# MAIN_POWER.net
KiCad netlist of a schematic drawn in Altium Designer
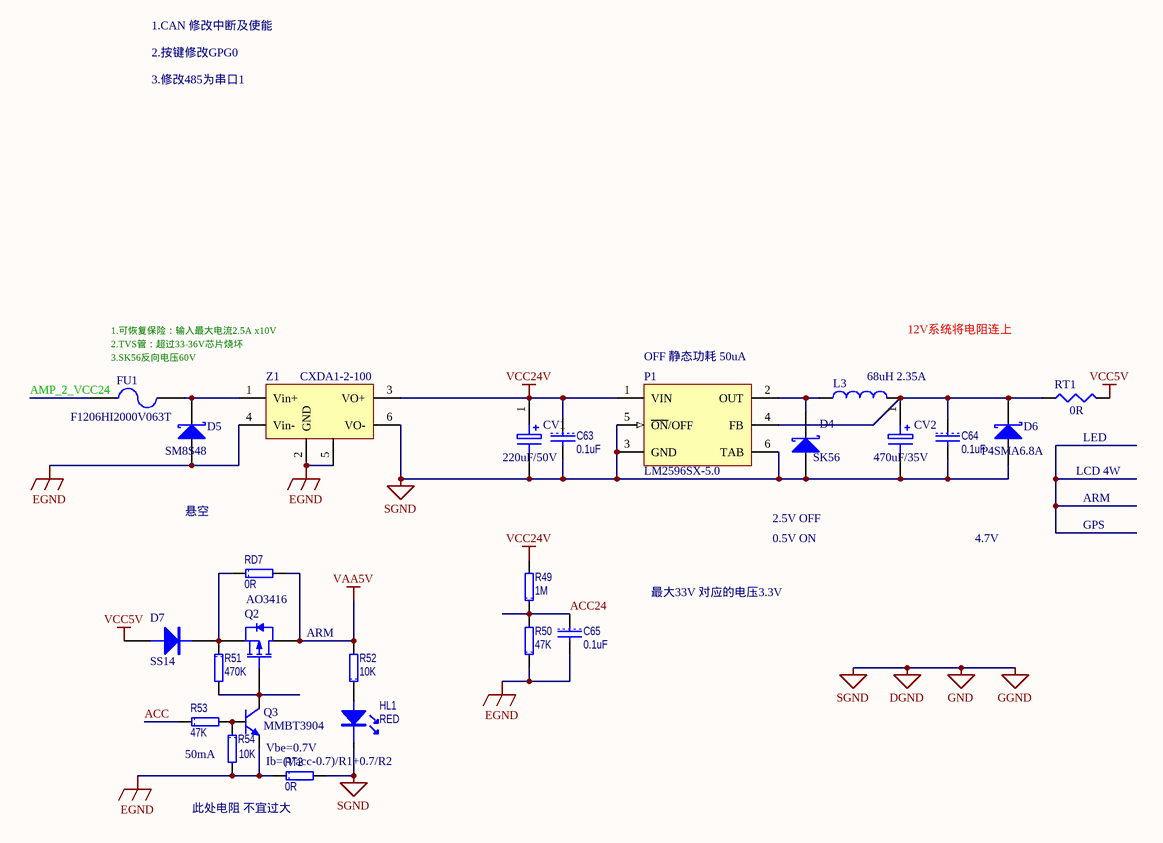
[diagram p0: MAIN POWER.SchDoc]

(export (version "E")
  (design (tool "Eeschema 10.0.6"))
  (components
    (comp (ref "C63")
      (value "0.1uF")
      (footprint "1608[0603]")
      (description "Capacitor")
      (fields (field (name "MANUFACTURER") "TDK"))
      (libsource (lib "*") (part "CAP"))
    )
    (comp (ref "C64")
      (value "0.1uF")
      (footprint "1608[0603]")
      (description "Capacitor")
      (fields (field (name "MANUFACTURER") "TDK"))
      (libsource (lib "*") (part "CAP"))
    )
    (comp (ref "C65")
      (value "0.1uF")
      (footprint "1608[0603]")
      (description "Capacitor")
      (fields (field (name "MANUFACTURER") "TDK"))
      (libsource (lib "*") (part "CAP"))
    )
    (comp (ref "CV1")
      (value "220uF/50V")
      (footprint "CAPPR5-10x20/H1.1")
      (description "aluminum electrolytic capacitor")
      (fields (field (name "MANUFACTURER") "Yageo"))
      (libsource (lib "*") (part "ELECTRO1"))
    )
    (comp (ref "CV2")
      (value "470uF/35V")
      (footprint "CAPPR5-10x20/H1.1")
      (description "aluminum electrolytic capacitor")
      (fields (field (name "MANUFACTURER") "Yageo"))
      (libsource (lib "*") (part "ELECTRO1"))
    )
    (comp (ref "D4")
      (value "SK56")
      (footprint "Miscellaneous Devices:DIODE_SMC")
      (description "肖特基二极管")
      (fields (field (name "PUBLISHER") "Altium Limited"))
      (libsource (lib "Miscellaneous Devices") (part "D Schottky"))
    )
    (comp (ref "D5")
      (value "SM8S48")
      (footprint "Miscellaneous Devices:DIODE_SMC")
      (description "TVS")
      (fields (field (name "PUBLISHER") "Altium Limited"))
      (libsource (lib "IR Rectifier - Schottky") (part "30BQ040"))
    )
    (comp (ref "D6")
      (value "P4SMA6.8A")
      (footprint "IR Rectifier - Schottky:SMA")
      (description "TVS")
      (fields (field (name "PUBLISHER") "Altium Limited"))
      (libsource (lib "IR Rectifier - Schottky") (part "30BQ040"))
    )
    (comp (ref "D7")
      (value "SS14")
      (footprint "SMA")
      (description "Diode")
      (libsource (lib "*") (part "DIODE"))
    )
    (comp (ref "FU1")
      (value "F1206HI2000V063T")
      (footprint "RAD-0.3")
      (description "FUSE")
      (fields (field (name "PUBLISHER") "Altium Limited"))
      (libsource (lib "Miscellaneous Devices") (part "Fuse 2"))
    )
    (comp (ref "HL1")
      (value "RED")
      (footprint "0805LED")
      (description "发光管")
      (libsource (lib "*") (part "LED"))
    )
    (comp (ref "L3")
      (value "68uH 2.35A")
      (footprint "INDP125125X85N")
      (description "Inductor")
      (fields (field (name "Comment") "B82477P4683M000") (field (name "PUBLISHER") "Altium Limited"))
      (libsource (lib "Miscellaneous Devices") (part "Inductor"))
    )
    (comp (ref "P1")
      (value "LM2596SX-5.0")
      (footprint "TS5B_N")
      (description "POWER")
      (fields
        (field (name "PARTNUMBER") "LM2596SX-12")
        (field (name "MANUFACTURER") "National Semiconductor")
        (field (name "PUBLISHER") "Altium Limited")
      )
      (libsource (lib "NSC Switcher") (part "LM2596SX-12"))
    )
    (comp (ref "Q2")
      (value "AO3416")
      (footprint "SOT23_N")
      (description "P-channel Enhancement Mode MOSFET")
      (fields (field (name "PUBLISHER") "Altium Limited"))
      (libsource (lib "Philips Discrete MOSFET - Low Power") (part "BSH205"))
    )
    (comp (ref "Q3") (value "MMBT3904") (footprint "SOT23-NPN") (libsource (lib "*") (part "MMBT3904")))
    (comp (ref "R49")
      (value "1M")
      (footprint "1608[0603]R")
      (description "RES")
      (fields (field (name "MANUFACTURER") "vishay"))
      (libsource (lib "*") (part "RES"))
    )
    (comp (ref "R50")
      (value "47K")
      (footprint "1608[0603]R")
      (description "RES")
      (fields (field (name "MANUFACTURER") "vishay"))
      (libsource (lib "*") (part "RES"))
    )
    (comp (ref "R51")
      (value "470K")
      (footprint "1608[0603]R")
      (description "RES")
      (fields (field (name "MANUFACTURER") "vishay"))
      (libsource (lib "*") (part "RES"))
    )
    (comp (ref "R52")
      (value "10K")
      (footprint "1608[0603]R")
      (description "RES")
      (fields (field (name "MANUFACTURER") "vishay"))
      (libsource (lib "*") (part "RES"))
    )
    (comp (ref "R53")
      (value "47K")
      (footprint "1608[0603]R")
      (description "RES")
      (fields (field (name "MANUFACTURER") "vishay"))
      (libsource (lib "*") (part "RES"))
    )
    (comp (ref "R54")
      (value "10K")
      (footprint "1608[0603]R")
      (description "RES")
      (fields (field (name "MANUFACTURER") "vishay"))
      (libsource (lib "*") (part "RES"))
    )
    (comp (ref "RD7")
      (value "0R")
      (footprint "1608[0603]RD")
      (description "RES")
      (fields (field (name "MANUFACTURER") "vishay"))
      (libsource (lib "*") (part "RES"))
    )
    (comp (ref "RT1")
      (value "0R")
      (footprint "2012[0805]")
      (description "电阻")
      (fields (field (name "MANUFACTURER") "Yageo") (field (name "PUBLISHER") "Altium Limited"))
      (libsource (lib "Miscellaneous Devices") (part "Res3"))
    )
    (comp (ref "RT2")
      (value "0R")
      (footprint "1608[0603]RD")
      (description "RES")
      (fields (field (name "MANUFACTURER") "vishay"))
      (libsource (lib "*") (part "RES"))
    )
    (comp (ref "Z1")
      (value "CXDA1-2-100")
      (footprint "CXDA1-2-100")
      (description "Filter")
      (libsource (lib "Schlib1") (part "CXDB"))
    )
  )
  (nets
    (net (code "1") (name "/ACC") (class "Default")
      (node (ref "R53") (pin "1") (pinfunction "1_1") (pintype "passive"))
    )
    (net (code "2") (name "/ACC24") (class "Default")
      (node (ref "C65") (pin "1") (pinfunction "1_1") (pintype "passive"))
      (node (ref "R49") (pin "1") (pinfunction "1_1") (pintype "passive"))
      (node (ref "R50") (pin "2") (pinfunction "2_2") (pintype "passive"))
    )
    (net (code "3") (name "/AMP_2_VCC24") (class "Default")
      (node (ref "FU1") (pin "1") (pinfunction "1_1") (pintype "passive"))
    )
    (net (code "4") (name "DGND") (class "Default")
      (node (ref "C63") (pin "2") (pinfunction "2_2") (pintype "passive"))
      (node (ref "C64") (pin "2") (pinfunction "2_2") (pintype "passive"))
      (node (ref "CV1") (pin "2") (pinfunction "2_2") (pintype "passive"))
      (node (ref "CV2") (pin "2") (pinfunction "2_2") (pintype "passive"))
      (node (ref "D4") (pin "1") (pinfunction "A_1") (pintype "passive"))
      (node (ref "D6") (pin "1") (pinfunction "A_1") (pintype "passive"))
      (node (ref "HL1") (pin "2") (pinfunction "2_2") (pintype "passive"))
      (node (ref "P1") (pin "3") (pinfunction "GND_3") (pintype "power_in"))
      (node (ref "P1") (pin "5") (pinfunction "~{ON}/OFF_5") (pintype "input"))
      (node (ref "P1") (pin "6") (pinfunction "TAB_6") (pintype "power_in"))
      (node (ref "RT2") (pin "2") (pinfunction "2_2") (pintype "passive"))
      (node (ref "Z1") (pin "6") (pinfunction "VO-_6") (pintype "passive"))
    )
    (net (code "5") (name "EGND") (class "Default")
      (node (ref "C65") (pin "2") (pinfunction "2_2") (pintype "passive"))
      (node (ref "D5") (pin "1") (pinfunction "A_1") (pintype "passive"))
      (node (ref "Q3") (pin "1") (pinfunction "1_1") (pintype "passive"))
      (node (ref "R50") (pin "1") (pinfunction "1_1") (pintype "passive"))
      (node (ref "R54") (pin "2") (pinfunction "2_2") (pintype "passive"))
      (node (ref "RT2") (pin "1") (pinfunction "1_1") (pintype "passive"))
      (node (ref "Z1") (pin "2") (pinfunction "GND_2") (pintype "passive"))
      (node (ref "Z1") (pin "4") (pinfunction "Vin-_4") (pintype "passive"))
      (node (ref "Z1") (pin "5") (pinfunction "GND_5") (pintype "passive"))
    )
    (net (code "6") (name "Net-(D4-K)") (class "Default")
      (node (ref "D4") (pin "2") (pinfunction "K_2") (pintype "passive"))
      (node (ref "L3") (pin "1") (pinfunction "1_1") (pintype "passive"))
      (node (ref "P1") (pin "2") (pinfunction "OUT_2") (pintype "power_in"))
    )
    (net (code "7") (name "Net-(D5-K)") (class "Default")
      (node (ref "D5") (pin "2") (pinfunction "K_2") (pintype "passive"))
      (node (ref "FU1") (pin "2") (pinfunction "2_2") (pintype "passive"))
      (node (ref "Z1") (pin "1") (pinfunction "Vin+_1") (pintype "passive"))
    )
    (net (code "8") (name "Net-(D6-K)") (class "Default")
      (node (ref "C64") (pin "1") (pinfunction "1_1") (pintype "passive"))
      (node (ref "CV2") (pin "1") (pinfunction "1_1") (pintype "passive"))
      (node (ref "D6") (pin "2") (pinfunction "K_2") (pintype "passive"))
      (node (ref "L3") (pin "2") (pinfunction "2_2") (pintype "passive"))
      (node (ref "P1") (pin "4") (pinfunction "FB_4") (pintype "passive"))
      (node (ref "RT1") (pin "1") (pinfunction "1_1") (pintype "passive"))
    )
    (net (code "9") (name "Net-(D7-K)") (class "Default")
      (node (ref "D7") (pin "2") (pinfunction "K_2") (pintype "passive"))
      (node (ref "Q2") (pin "2") (pinfunction "S_2") (pintype "passive"))
      (node (ref "R51") (pin "1") (pinfunction "1_1") (pintype "passive"))
      (node (ref "RD7") (pin "1") (pinfunction "1_1") (pintype "passive"))
    )
    (net (code "10") (name "Net-(HL1-Pad1)") (class "Default")
      (node (ref "HL1") (pin "1") (pinfunction "1_1") (pintype "passive"))
      (node (ref "R52") (pin "1") (pinfunction "1_1") (pintype "passive"))
    )
    (net (code "11") (name "Net-(Q2-G)") (class "Default")
      (node (ref "Q2") (pin "1") (pinfunction "G_1") (pintype "passive"))
      (node (ref "Q3") (pin "3") (pinfunction "3_3") (pintype "passive"))
      (node (ref "R51") (pin "2") (pinfunction "2_2") (pintype "passive"))
    )
    (net (code "12") (name "Net-(Q3-Pad2)") (class "Default")
      (node (ref "Q3") (pin "2") (pinfunction "2_2") (pintype "passive"))
      (node (ref "R53") (pin "2") (pinfunction "2_2") (pintype "passive"))
      (node (ref "R54") (pin "1") (pinfunction "1_1") (pintype "passive"))
    )
    (net (code "13") (name "VAA5V") (class "Default")
      (node (ref "Q2") (pin "3") (pinfunction "D_3") (pintype "passive"))
      (node (ref "R52") (pin "2") (pinfunction "2_2") (pintype "passive"))
      (node (ref "RD7") (pin "2") (pinfunction "2_2") (pintype "passive"))
    )
    (net (code "14") (name "VCC5V") (class "Default")
      (node (ref "D7") (pin "1") (pinfunction "A_1") (pintype "passive"))
      (node (ref "RT1") (pin "2") (pinfunction "2_2") (pintype "passive"))
    )
    (net (code "15") (name "VCC24V") (class "Default")
      (node (ref "C63") (pin "1") (pinfunction "1_1") (pintype "passive"))
      (node (ref "CV1") (pin "1") (pinfunction "1_1") (pintype "passive"))
      (node (ref "P1") (pin "1") (pinfunction "VIN_1") (pintype "power_in"))
      (node (ref "R49") (pin "2") (pinfunction "2_2") (pintype "passive"))
      (node (ref "Z1") (pin "3") (pinfunction "VO+_3") (pintype "passive"))
    )
  )
)
